# STM32G030C8.net
KiCad netlist of a schematic drawn in Altium Designer
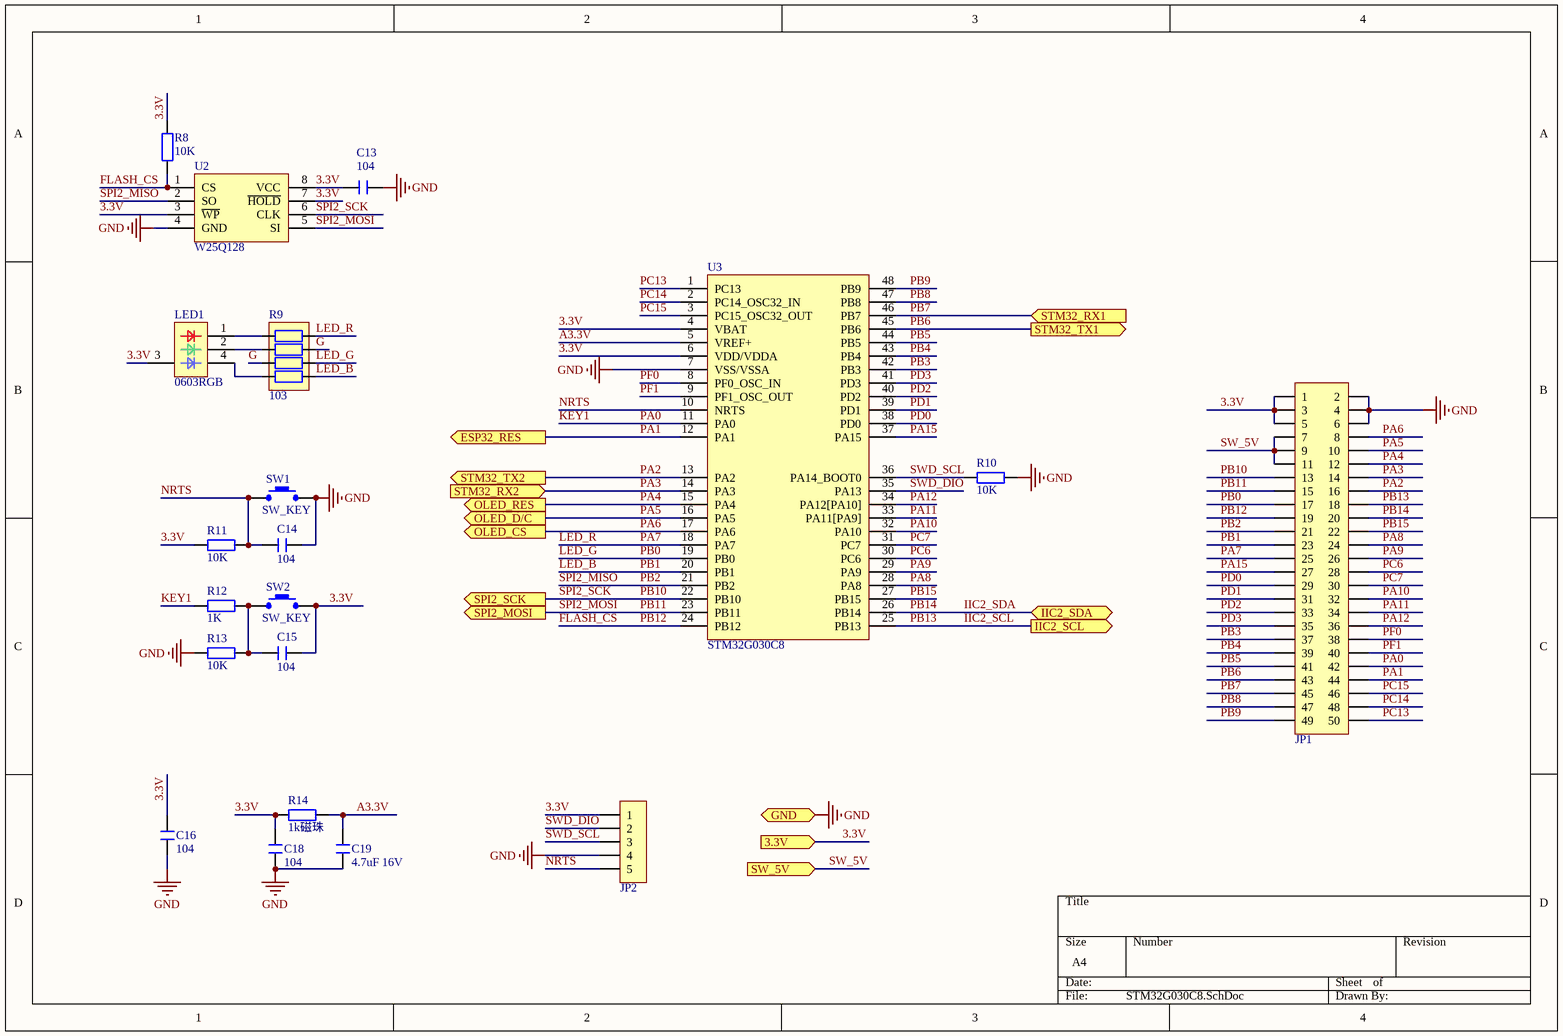
[diagram p0: STM32G030C8.SchDoc]

(export (version "E")
  (design (tool "Eeschema 10.0.6"))
  (components
    (comp (ref "C13")
      (value "104")
      (footprint "C 0603_L")
      (description "贴片电容")
      (libsource (lib "0.1 - 电阻-电容-电感") (part "C"))
    )
    (comp (ref "C14")
      (value "104")
      (footprint "C 0603_L")
      (description "贴片电容")
      (libsource (lib "0.1 - 电阻-电容-电感") (part "C"))
    )
    (comp (ref "C15")
      (value "104")
      (footprint "C 0603_L")
      (description "贴片电容")
      (libsource (lib "0.1 - 电阻-电容-电感") (part "C"))
    )
    (comp (ref "C16")
      (value "104")
      (footprint "C 0603_L")
      (description "贴片电容")
      (libsource (lib "0.1 - 电阻-电容-电感") (part "C"))
    )
    (comp (ref "C18")
      (value "104")
      (footprint "C 0603_L")
      (description "贴片电容")
      (libsource (lib "0.1 - 电阻-电容-电感") (part "C"))
    )
    (comp (ref "C19")
      (value "4.7uF 16V")
      (footprint "C 0603_L")
      (description "贴片电容")
      (libsource (lib "0.1 - 电阻-电容-电感") (part "C"))
    )
    (comp (ref "JP1")
      (value "Header 2X25")
      (footprint "CHE2*25")
      (description "25*2P接插件")
      (fields (field (name "版权归属") "封装库来自淘宝 ID：黄晶宝石"))
      (libsource (lib "5.4 - 接插件-脚距2.54 (100mil) ") (part "Header 25X2"))
    )
    (comp (ref "JP2")
      (value "HDR-1X5")
      (footprint "CHE1*5")
      (description "5P接插件")
      (fields (field (name "版权归属") "封装库来自淘宝 ID：黄晶宝石"))
      (libsource (lib "5.4 - 接插件-脚距2.54 (100mil) ") (part "Header 5"))
    )
    (comp (ref "LED1")
      (value "0603RGB")
      (footprint "0603RGB")
      (libsource (lib "0.3 - LED发光二极管") (part "0603RGB"))
    )
    (comp (ref "R8")
      (value "10K")
      (footprint "R 0603_L")
      (description "贴片电阻")
      (libsource (lib "0.1 - 电阻-电容-电感") (part "R"))
    )
    (comp (ref "R9")
      (value "103")
      (footprint "RCA-8P4R-0402")
      (description "贴片排阻")
      (libsource (lib "0.1 - 电阻-电容-电感") (part "R-8P4R"))
    )
    (comp (ref "R10")
      (value "10K")
      (footprint "R 0603_L")
      (description "贴片电阻")
      (libsource (lib "0.1 - 电阻-电容-电感") (part "R"))
    )
    (comp (ref "R11")
      (value "10K")
      (footprint "R 0603_L")
      (description "贴片电阻")
      (libsource (lib "0.1 - 电阻-电容-电感") (part "R"))
    )
    (comp (ref "R12")
      (value "1K")
      (footprint "R 0603_L")
      (description "贴片电阻")
      (libsource (lib "0.1 - 电阻-电容-电感") (part "R"))
    )
    (comp (ref "R13")
      (value "10K")
      (footprint "R 0603_L")
      (description "贴片电阻")
      (libsource (lib "0.1 - 电阻-电容-电感") (part "R"))
    )
    (comp (ref "R14")
      (value "1k磁珠")
      (footprint "R 0603_L")
      (description "贴片电阻")
      (libsource (lib "0.1 - 电阻-电容-电感") (part "R"))
    )
    (comp (ref "SW1")
      (value "SW_KEY")
      (footprint "TSW SMD-4*4*1.5")
      (libsource (lib "0.7 - 常用按键-开关-蜂鸣器-电池") (part "SW_KEY"))
    )
    (comp (ref "SW2")
      (value "SW_KEY")
      (footprint "TSW SMD-4*4*1.5")
      (libsource (lib "0.7 - 常用按键-开关-蜂鸣器-电池") (part "SW_KEY"))
    )
    (comp (ref "U2")
      (value "W25Q128")
      (footprint "SOP8W_L")
      (libsource (lib "2.0 - FLASH存储器") (part "W25Q128"))
    )
    (comp (ref "U3")
      (value "STM32G030C8")
      (footprint "LQFP48_L")
      (description "STM32G0系列")
      (libsource (lib "STM32G0系列") (part "STM32G030C8"))
    )
  )
  (nets
    (net (code "1") (name "/3.3V") (class "Default")
      (node (ref "C13") (pin "1") (pinfunction "1_1") (pintype "passive"))
      (node (ref "C15") (pin "1") (pinfunction "1_1") (pintype "passive"))
      (node (ref "C16") (pin "2") (pinfunction "2_2") (pintype "passive"))
      (node (ref "C18") (pin "2") (pinfunction "2_2") (pintype "passive"))
      (node (ref "JP1") (pin "1") (pinfunction "1_1") (pintype "passive"))
      (node (ref "JP1") (pin "3") (pinfunction "3_3") (pintype "passive"))
      (node (ref "JP1") (pin "5") (pinfunction "5_5") (pintype "passive"))
      (node (ref "JP2") (pin "1") (pinfunction "1_1") (pintype "passive"))
      (node (ref "LED1") (pin "3") (pinfunction "VCC_3") (pintype "passive"))
      (node (ref "R11") (pin "2") (pinfunction "2_2") (pintype "passive"))
      (node (ref "R14") (pin "1") (pinfunction "1_1") (pintype "passive"))
      (node (ref "R8") (pin "2") (pinfunction "2_2") (pintype "passive"))
      (node (ref "SW2") (pin "4") (pinfunction "D_4") (pintype "passive"))
      (node (ref "U2") (pin "3") (pinfunction "~{WP}_3") (pintype "passive"))
      (node (ref "U2") (pin "7") (pinfunction "~{HOLD}_7") (pintype "passive"))
      (node (ref "U2") (pin "8") (pinfunction "VCC_8") (pintype "passive"))
      (node (ref "U3") (pin "4") (pinfunction "VBAT_4") (pintype "passive"))
      (node (ref "U3") (pin "6") (pinfunction "VDD/VDDA_6") (pintype "passive"))
    )
    (net (code "2") (name "/A3.3V") (class "Default")
      (node (ref "C19") (pin "2") (pinfunction "2_2") (pintype "passive"))
      (node (ref "R14") (pin "2") (pinfunction "2_2") (pintype "passive"))
      (node (ref "U3") (pin "5") (pinfunction "VREF+_5") (pintype "passive"))
    )
    (net (code "3") (name "/FLASH_CS") (class "Default")
      (node (ref "JP1") (pin "19") (pinfunction "19_19") (pintype "passive"))
      (node (ref "R8") (pin "1") (pinfunction "1_1") (pintype "passive"))
      (node (ref "U2") (pin "1") (pinfunction "CS_1") (pintype "passive"))
      (node (ref "U3") (pin "24") (pinfunction "PB12_24") (pintype "passive"))
    )
    (net (code "4") (name "/G") (class "Default")
      (node (ref "R9") (pin "3") (pinfunction "3_3") (pintype "passive"))
      (node (ref "R9") (pin "7") (pinfunction "7_7") (pintype "passive"))
    )
    (net (code "5") (name "/IIC2_SCL") (class "Default")
      (node (ref "JP1") (pin "18") (pinfunction "18_18") (pintype "passive"))
      (node (ref "U3") (pin "25") (pinfunction "PB13_25") (pintype "passive"))
    )
    (net (code "6") (name "/IIC2_SDA") (class "Default")
      (node (ref "JP1") (pin "20") (pinfunction "20_20") (pintype "passive"))
      (node (ref "U3") (pin "26") (pinfunction "PB14_26") (pintype "passive"))
    )
    (net (code "7") (name "/KEY1") (class "Default")
      (node (ref "JP1") (pin "42") (pinfunction "42_42") (pintype "passive"))
      (node (ref "R12") (pin "2") (pinfunction "2_2") (pintype "passive"))
      (node (ref "U3") (pin "11") (pinfunction "PA0_11") (pintype "passive"))
    )
    (net (code "8") (name "/LED_B") (class "Default")
      (node (ref "JP1") (pin "23") (pinfunction "23_23") (pintype "passive"))
      (node (ref "R9") (pin "5") (pinfunction "5_5") (pintype "passive"))
      (node (ref "U3") (pin "20") (pinfunction "PB1_20") (pintype "passive"))
    )
    (net (code "9") (name "/LED_G") (class "Default")
      (node (ref "JP1") (pin "17") (pinfunction "17_17") (pintype "passive"))
      (node (ref "R9") (pin "6") (pinfunction "6_6") (pintype "passive"))
      (node (ref "U3") (pin "19") (pinfunction "PB0_19") (pintype "passive"))
    )
    (net (code "10") (name "/LED_R") (class "Default")
      (node (ref "JP1") (pin "25") (pinfunction "25_25") (pintype "passive"))
      (node (ref "R9") (pin "8") (pinfunction "8_8") (pintype "passive"))
      (node (ref "U3") (pin "18") (pinfunction "PA7_18") (pintype "passive"))
    )
    (net (code "11") (name "/NRTS") (class "Default")
      (node (ref "C14") (pin "2") (pinfunction "2_2") (pintype "passive"))
      (node (ref "JP2") (pin "5") (pinfunction "5_5") (pintype "passive"))
      (node (ref "R11") (pin "1") (pinfunction "1_1") (pintype "passive"))
      (node (ref "SW1") (pin "1") (pinfunction "A_1") (pintype "passive"))
      (node (ref "U3") (pin "10") (pinfunction "NRTS_10") (pintype "passive"))
    )
    (net (code "12") (name "/PA1") (class "Default")
      (node (ref "JP1") (pin "44") (pinfunction "44_44") (pintype "passive"))
      (node (ref "U3") (pin "12") (pinfunction "PA1_12") (pintype "passive"))
    )
    (net (code "13") (name "/PA2") (class "Default")
      (node (ref "JP1") (pin "16") (pinfunction "16_16") (pintype "passive"))
      (node (ref "U3") (pin "13") (pinfunction "PA2_13") (pintype "passive"))
    )
    (net (code "14") (name "/PA3") (class "Default")
      (node (ref "JP1") (pin "14") (pinfunction "14_14") (pintype "passive"))
      (node (ref "U3") (pin "14") (pinfunction "PA3_14") (pintype "passive"))
    )
    (net (code "15") (name "/PA4") (class "Default")
      (node (ref "JP1") (pin "12") (pinfunction "12_12") (pintype "passive"))
      (node (ref "U3") (pin "15") (pinfunction "PA4_15") (pintype "passive"))
    )
    (net (code "16") (name "/PA5") (class "Default")
      (node (ref "JP1") (pin "10") (pinfunction "10_10") (pintype "passive"))
      (node (ref "U3") (pin "16") (pinfunction "PA5_16") (pintype "passive"))
    )
    (net (code "17") (name "/PA6") (class "Default")
      (node (ref "JP1") (pin "8") (pinfunction "8_8") (pintype "passive"))
      (node (ref "U3") (pin "17") (pinfunction "PA6_17") (pintype "passive"))
    )
    (net (code "18") (name "/PA8") (class "Default")
      (node (ref "JP1") (pin "24") (pinfunction "24_24") (pintype "passive"))
      (node (ref "U3") (pin "28") (pinfunction "PA8_28") (pintype "passive"))
    )
    (net (code "19") (name "/PA9") (class "Default")
      (node (ref "JP1") (pin "26") (pinfunction "26_26") (pintype "passive"))
      (node (ref "U3") (pin "29") (pinfunction "PA9_29") (pintype "passive"))
    )
    (net (code "20") (name "/PA10") (class "Default")
      (node (ref "JP1") (pin "32") (pinfunction "32_32") (pintype "passive"))
      (node (ref "U3") (pin "32") (pinfunction "PA10_32") (pintype "passive"))
    )
    (net (code "21") (name "/PA11") (class "Default")
      (node (ref "JP1") (pin "34") (pinfunction "34_34") (pintype "passive"))
      (node (ref "U3") (pin "33") (pinfunction "PA11[PA9]_33") (pintype "passive"))
    )
    (net (code "22") (name "/PA12") (class "Default")
      (node (ref "JP1") (pin "36") (pinfunction "36_36") (pintype "passive"))
      (node (ref "U3") (pin "34") (pinfunction "PA12[PA10]_34") (pintype "passive"))
    )
    (net (code "23") (name "/PA15") (class "Default")
      (node (ref "JP1") (pin "27") (pinfunction "27_27") (pintype "passive"))
      (node (ref "U3") (pin "37") (pinfunction "PA15_37") (pintype "passive"))
    )
    (net (code "24") (name "/PB2") (class "Default")
      (node (ref "JP1") (pin "21") (pinfunction "21_21") (pintype "passive"))
      (node (ref "U2") (pin "2") (pinfunction "SO_2") (pintype "passive"))
      (node (ref "U3") (pin "21") (pinfunction "PB2_21") (pintype "passive"))
    )
    (net (code "25") (name "/PB3") (class "Default")
      (node (ref "JP1") (pin "37") (pinfunction "37_37") (pintype "passive"))
      (node (ref "U3") (pin "42") (pinfunction "PB3_42") (pintype "passive"))
    )
    (net (code "26") (name "/PB4") (class "Default")
      (node (ref "JP1") (pin "39") (pinfunction "39_39") (pintype "passive"))
      (node (ref "U3") (pin "43") (pinfunction "PB4_43") (pintype "passive"))
    )
    (net (code "27") (name "/PB5") (class "Default")
      (node (ref "JP1") (pin "41") (pinfunction "41_41") (pintype "passive"))
      (node (ref "U3") (pin "44") (pinfunction "PB5_44") (pintype "passive"))
    )
    (net (code "28") (name "/PB6") (class "Default")
      (node (ref "JP1") (pin "43") (pinfunction "43_43") (pintype "passive"))
      (node (ref "U3") (pin "45") (pinfunction "PB6_45") (pintype "passive"))
    )
    (net (code "29") (name "/PB7") (class "Default")
      (node (ref "JP1") (pin "45") (pinfunction "45_45") (pintype "passive"))
      (node (ref "U3") (pin "46") (pinfunction "PB7_46") (pintype "passive"))
    )
    (net (code "30") (name "/PB8") (class "Default")
      (node (ref "JP1") (pin "47") (pinfunction "47_47") (pintype "passive"))
      (node (ref "U3") (pin "47") (pinfunction "PB8_47") (pintype "passive"))
    )
    (net (code "31") (name "/PB9") (class "Default")
      (node (ref "JP1") (pin "49") (pinfunction "49_49") (pintype "passive"))
      (node (ref "U3") (pin "48") (pinfunction "PB9_48") (pintype "passive"))
    )
    (net (code "32") (name "/PB10") (class "Default")
      (node (ref "JP1") (pin "13") (pinfunction "13_13") (pintype "passive"))
      (node (ref "U2") (pin "6") (pinfunction "CLK_6") (pintype "passive"))
      (node (ref "U3") (pin "22") (pinfunction "PB10_22") (pintype "passive"))
    )
    (net (code "33") (name "/PB11") (class "Default")
      (node (ref "JP1") (pin "15") (pinfunction "15_15") (pintype "passive"))
      (node (ref "U2") (pin "5") (pinfunction "SI_5") (pintype "passive"))
      (node (ref "U3") (pin "23") (pinfunction "PB11_23") (pintype "passive"))
    )
    (net (code "34") (name "/PB15") (class "Default")
      (node (ref "JP1") (pin "22") (pinfunction "22_22") (pintype "passive"))
      (node (ref "U3") (pin "27") (pinfunction "PB15_27") (pintype "passive"))
    )
    (net (code "35") (name "/PC6") (class "Default")
      (node (ref "JP1") (pin "28") (pinfunction "28_28") (pintype "passive"))
      (node (ref "U3") (pin "30") (pinfunction "PC6_30") (pintype "passive"))
    )
    (net (code "36") (name "/PC7") (class "Default")
      (node (ref "JP1") (pin "30") (pinfunction "30_30") (pintype "passive"))
      (node (ref "U3") (pin "31") (pinfunction "PC7_31") (pintype "passive"))
    )
    (net (code "37") (name "/PC13") (class "Default")
      (node (ref "JP1") (pin "50") (pinfunction "50_50") (pintype "passive"))
      (node (ref "U3") (pin "1") (pinfunction "PC13_1") (pintype "passive"))
    )
    (net (code "38") (name "/PC14") (class "Default")
      (node (ref "JP1") (pin "48") (pinfunction "48_48") (pintype "passive"))
      (node (ref "U3") (pin "2") (pinfunction "PC14_OSC32_IN_2") (pintype "passive"))
    )
    (net (code "39") (name "/PC15") (class "Default")
      (node (ref "JP1") (pin "46") (pinfunction "46_46") (pintype "passive"))
      (node (ref "U3") (pin "3") (pinfunction "PC15_OSC32_OUT_3") (pintype "passive"))
    )
    (net (code "40") (name "/PD0") (class "Default")
      (node (ref "JP1") (pin "29") (pinfunction "29_29") (pintype "passive"))
      (node (ref "U3") (pin "38") (pinfunction "PD0_38") (pintype "passive"))
    )
    (net (code "41") (name "/PD1") (class "Default")
      (node (ref "JP1") (pin "31") (pinfunction "31_31") (pintype "passive"))
      (node (ref "U3") (pin "39") (pinfunction "PD1_39") (pintype "passive"))
    )
    (net (code "42") (name "/PD2") (class "Default")
      (node (ref "JP1") (pin "33") (pinfunction "33_33") (pintype "passive"))
      (node (ref "U3") (pin "40") (pinfunction "PD2_40") (pintype "passive"))
    )
    (net (code "43") (name "/PD3") (class "Default")
      (node (ref "JP1") (pin "35") (pinfunction "35_35") (pintype "passive"))
      (node (ref "U3") (pin "41") (pinfunction "PD3_41") (pintype "passive"))
    )
    (net (code "44") (name "/PF0") (class "Default")
      (node (ref "JP1") (pin "38") (pinfunction "38_38") (pintype "passive"))
      (node (ref "U3") (pin "8") (pinfunction "PF0_OSC_IN_8") (pintype "passive"))
    )
    (net (code "45") (name "/PF1") (class "Default")
      (node (ref "JP1") (pin "40") (pinfunction "40_40") (pintype "passive"))
      (node (ref "U3") (pin "9") (pinfunction "PF1_OSC_OUT_9") (pintype "passive"))
    )
    (net (code "46") (name "/SWD_DIO") (class "Default")
      (node (ref "JP2") (pin "2") (pinfunction "2_2") (pintype "passive"))
      (node (ref "U3") (pin "35") (pinfunction "PA13_35") (pintype "passive"))
    )
    (net (code "47") (name "/SWD_SCL") (class "Default")
      (node (ref "JP2") (pin "3") (pinfunction "3_3") (pintype "passive"))
      (node (ref "R10") (pin "2") (pinfunction "2_2") (pintype "passive"))
      (node (ref "U3") (pin "36") (pinfunction "PA14_BOOT0_36") (pintype "passive"))
    )
    (net (code "48") (name "/SW_5V") (class "Default")
      (node (ref "JP1") (pin "11") (pinfunction "11_11") (pintype "passive"))
      (node (ref "JP1") (pin "7") (pinfunction "7_7") (pintype "passive"))
      (node (ref "JP1") (pin "9") (pinfunction "9_9") (pintype "passive"))
    )
    (net (code "49") (name "GND") (class "Default")
      (node (ref "C13") (pin "2") (pinfunction "2_2") (pintype "passive"))
      (node (ref "C14") (pin "1") (pinfunction "1_1") (pintype "passive"))
      (node (ref "C16") (pin "1") (pinfunction "1_1") (pintype "passive"))
      (node (ref "C18") (pin "1") (pinfunction "1_1") (pintype "passive"))
      (node (ref "C19") (pin "1") (pinfunction "1_1") (pintype "passive"))
      (node (ref "JP1") (pin "2") (pinfunction "2_2") (pintype "passive"))
      (node (ref "JP1") (pin "4") (pinfunction "4_4") (pintype "passive"))
      (node (ref "JP1") (pin "6") (pinfunction "6_6") (pintype "passive"))
      (node (ref "JP2") (pin "4") (pinfunction "4_4") (pintype "passive"))
      (node (ref "R10") (pin "1") (pinfunction "1_1") (pintype "passive"))
      (node (ref "R13") (pin "2") (pinfunction "2_2") (pintype "passive"))
      (node (ref "SW1") (pin "4") (pinfunction "D_4") (pintype "passive"))
      (node (ref "U2") (pin "4") (pinfunction "GND_4") (pintype "passive"))
      (node (ref "U3") (pin "7") (pinfunction "VSS/VSSA_7") (pintype "passive"))
    )
    (net (code "50") (name "Net-(LED1-B)") (class "Default")
      (node (ref "LED1") (pin "4") (pinfunction "B_4") (pintype "passive"))
      (node (ref "R9") (pin "4") (pinfunction "4_4") (pintype "passive"))
    )
    (net (code "51") (name "Net-(LED1-G)") (class "Default")
      (node (ref "LED1") (pin "2") (pinfunction "G_2") (pintype "passive"))
      (node (ref "R9") (pin "2") (pinfunction "2_2") (pintype "passive"))
    )
    (net (code "52") (name "Net-(LED1-R)") (class "Default")
      (node (ref "LED1") (pin "1") (pinfunction "R_1") (pintype "passive"))
      (node (ref "R9") (pin "1") (pinfunction "1_1") (pintype "passive"))
    )
    (net (code "53") (name "Net-(SW2-A)") (class "Default")
      (node (ref "C15") (pin "2") (pinfunction "2_2") (pintype "passive"))
      (node (ref "R12") (pin "1") (pinfunction "1_1") (pintype "passive"))
      (node (ref "R13") (pin "1") (pinfunction "1_1") (pintype "passive"))
      (node (ref "SW2") (pin "1") (pinfunction "A_1") (pintype "passive"))
    )
  )
)
